# voltage_regulator.net
KiCad netlist of a schematic drawn in Altium Designer
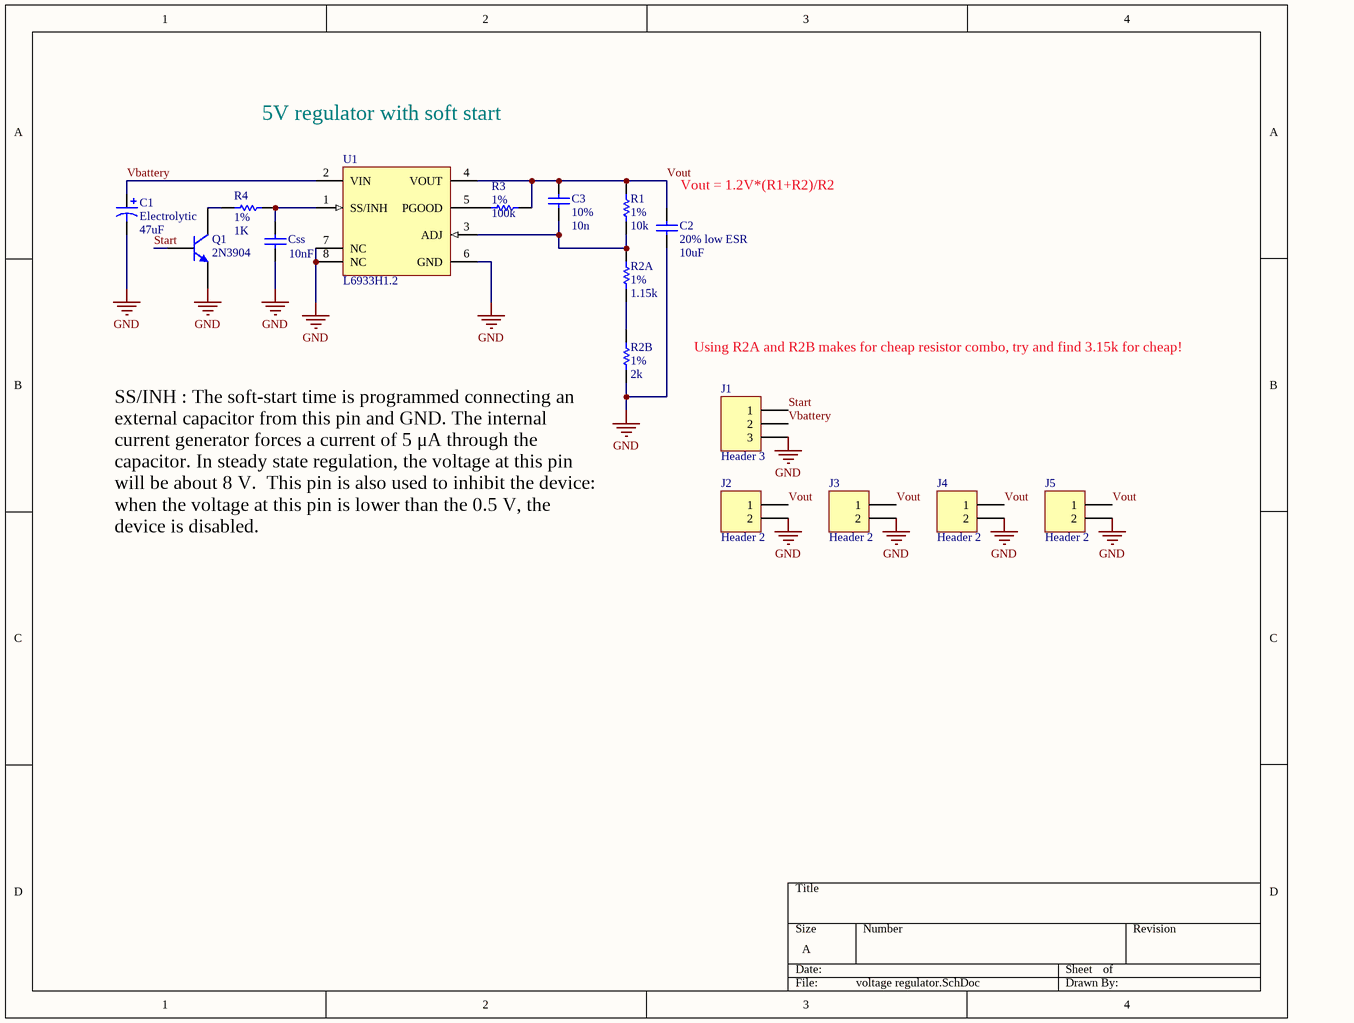
[diagram p0: voltage regulator.SchDoc]

(export (version "E")
  (design (tool "Eeschema 10.0.6"))
  (components
    (comp (ref "C1")
      (value "Electrolytic")
      (footprint "RAD-0.3")
      (description "Polarized Capacitor (Radial)")
      (fields (field (name "ALTIUM_VALUE") "47uF") (field (name "PUBLISHER") "Altium Limited"))
      (libsource (lib "Miscellaneous Devices") (part "Cap Pol1"))
    )
    (comp (ref "C2")
      (value "20% low ESR")
      (footprint "C1206")
      (description "Capacitor")
      (fields (field (name "ALTIUM_VALUE") "10uF") (field (name "PUBLISHER") "Altium Limited"))
      (libsource (lib "Miscellaneous Devices") (part "Cap"))
    )
    (comp (ref "C3")
      (value "10%")
      (footprint "6-0805_M")
      (description "Capacitor")
      (fields (field (name "ALTIUM_VALUE") "10n") (field (name "PUBLISHER") "Altium Limited"))
      (libsource (lib "Miscellaneous Devices") (part "Cap"))
    )
    (comp (ref "Css")
      (value "10nF")
      (footprint "6-0805_M")
      (description "Capacitor")
      (fields (field (name "Comment") "10%, 10 nF, 16 V (min)") (field (name "PUBLISHER") "Altium Limited"))
      (libsource (lib "Miscellaneous Devices") (part "Cap"))
    )
    (comp (ref "J1")
      (value "Header 3")
      (footprint "HDR1X3")
      (description "Header, 3-Pin")
      (fields (field (name "PUBLISHER") "Altium Limited"))
      (libsource (lib "Miscellaneous Connectors") (part "Header 3"))
    )
    (comp (ref "J2")
      (value "Header 2")
      (footprint "HDR1X2")
      (description "Header, 2-Pin")
      (fields (field (name "PUBLISHER") "Altium Limited"))
      (libsource (lib "Miscellaneous Connectors") (part "Header 2"))
    )
    (comp (ref "J3")
      (value "Header 2")
      (footprint "HDR1X2")
      (description "Header, 2-Pin")
      (fields (field (name "PUBLISHER") "Altium Limited"))
      (libsource (lib "Miscellaneous Connectors") (part "Header 2"))
    )
    (comp (ref "J4")
      (value "Header 2")
      (footprint "HDR1X2")
      (description "Header, 2-Pin")
      (fields (field (name "PUBLISHER") "Altium Limited"))
      (libsource (lib "Miscellaneous Connectors") (part "Header 2"))
    )
    (comp (ref "J5")
      (value "Header 2")
      (footprint "HDR1X2")
      (description "Header, 2-Pin")
      (fields (field (name "PUBLISHER") "Altium Limited"))
      (libsource (lib "Miscellaneous Connectors") (part "Header 2"))
    )
    (comp (ref "Q1")
      (value "2N3904")
      (footprint "TO-92A")
      (description "NPN General Purpose Amplifier")
      (fields (field (name "PUBLISHER") "Altium Limited"))
      (libsource (lib "Miscellaneous Devices") (part "2N3904"))
    )
    (comp (ref "R1")
      (value "1%")
      (footprint "6-0805_M")
      (description "Resistor")
      (fields (field (name "ALTIUM_VALUE") "10k") (field (name "PUBLISHER") "Altium Limited"))
      (libsource (lib "Miscellaneous Devices") (part "Res1"))
    )
    (comp (ref "R2A")
      (value "1%")
      (footprint "6-0805_M")
      (description "Resistor")
      (fields (field (name "ALTIUM_VALUE") "1.15k") (field (name "PUBLISHER") "Altium Limited"))
      (libsource (lib "Miscellaneous Devices") (part "Res1"))
    )
    (comp (ref "R2B")
      (value "1%")
      (footprint "6-0805_M")
      (description "Resistor")
      (fields (field (name "ALTIUM_VALUE") "2k") (field (name "PUBLISHER") "Altium Limited"))
      (libsource (lib "Miscellaneous Devices") (part "Res1"))
    )
    (comp (ref "R3")
      (value "1%")
      (footprint "6-0805_M")
      (description "Resistor")
      (fields (field (name "ALTIUM_VALUE") "100k") (field (name "PUBLISHER") "Altium Limited"))
      (libsource (lib "Miscellaneous Devices") (part "Res1"))
    )
    (comp (ref "R4")
      (value "1%")
      (footprint "6-0805_M")
      (description "Resistor")
      (fields (field (name "ALTIUM_VALUE") "1K") (field (name "PUBLISHER") "Altium Limited"))
      (libsource (lib "Miscellaneous Devices") (part "Res1"))
    )
    (comp (ref "U1")
      (value "L6933H1.2")
      (footprint "SO8_M")
      (description "High Performance 2A ULDO Linear Regulator with Soft Start, 8-Pin SO")
      (libsource (lib "Altium Content Vault") (part "CMP-0240-00057-1"))
    )
  )
  (nets
    (net (code "1") (name "/Start") (class "Default")
      (node (ref "J1") (pin "1") (pinfunction "1_1") (pintype "passive"))
      (node (ref "Q1") (pin "2") (pinfunction "B_2") (pintype "passive"))
    )
    (net (code "2") (name "/Vbattery") (class "Default")
      (node (ref "C1") (pin "1") (pinfunction "1_1") (pintype "passive"))
      (node (ref "J1") (pin "2") (pinfunction "2_2") (pintype "passive"))
      (node (ref "U1") (pin "2") (pinfunction "VIN_2") (pintype "power_in"))
    )
    (net (code "3") (name "/Vout") (class "Default")
      (node (ref "C2") (pin "2") (pinfunction "2_2") (pintype "passive"))
      (node (ref "C3") (pin "2") (pinfunction "2_2") (pintype "passive"))
      (node (ref "J2") (pin "1") (pinfunction "1_1") (pintype "passive"))
      (node (ref "J3") (pin "1") (pinfunction "1_1") (pintype "passive"))
      (node (ref "J4") (pin "1") (pinfunction "1_1") (pintype "passive"))
      (node (ref "J5") (pin "1") (pinfunction "1_1") (pintype "passive"))
      (node (ref "R1") (pin "2") (pinfunction "2_2") (pintype "passive"))
      (node (ref "R3") (pin "2") (pinfunction "2_2") (pintype "passive"))
      (node (ref "U1") (pin "4") (pinfunction "VOUT_4") (pintype "power_in"))
    )
    (net (code "4") (name "GND") (class "Default")
      (node (ref "C1") (pin "2") (pinfunction "2_2") (pintype "passive"))
      (node (ref "C2") (pin "1") (pinfunction "1_1") (pintype "passive"))
      (node (ref "Css") (pin "1") (pinfunction "1_1") (pintype "passive"))
      (node (ref "J1") (pin "3") (pinfunction "3_3") (pintype "passive"))
      (node (ref "J2") (pin "2") (pinfunction "2_2") (pintype "passive"))
      (node (ref "J3") (pin "2") (pinfunction "2_2") (pintype "passive"))
      (node (ref "J4") (pin "2") (pinfunction "2_2") (pintype "passive"))
      (node (ref "J5") (pin "2") (pinfunction "2_2") (pintype "passive"))
      (node (ref "Q1") (pin "1") (pinfunction "E_1") (pintype "passive"))
      (node (ref "R2B") (pin "1") (pinfunction "1_1") (pintype "passive"))
      (node (ref "U1") (pin "6") (pinfunction "GND_6") (pintype "power_in"))
      (node (ref "U1") (pin "7") (pinfunction "NC_7") (pintype "passive"))
      (node (ref "U1") (pin "8") (pinfunction "NC_8") (pintype "passive"))
    )
    (net (code "5") (name "Net-(Q1-C)") (class "Default")
      (node (ref "Q1") (pin "3") (pinfunction "C_3") (pintype "passive"))
      (node (ref "R4") (pin "1") (pinfunction "1_1") (pintype "passive"))
    )
    (net (code "6") (name "Net-(R2A-Pad1)") (class "Default")
      (node (ref "R2A") (pin "1") (pinfunction "1_1") (pintype "passive"))
      (node (ref "R2B") (pin "2") (pinfunction "2_2") (pintype "passive"))
    )
    (net (code "7") (name "Net-(U1-ADJ)") (class "Default")
      (node (ref "C3") (pin "1") (pinfunction "1_1") (pintype "passive"))
      (node (ref "R1") (pin "1") (pinfunction "1_1") (pintype "passive"))
      (node (ref "R2A") (pin "2") (pinfunction "2_2") (pintype "passive"))
      (node (ref "U1") (pin "3") (pinfunction "ADJ_3") (pintype "input"))
    )
    (net (code "8") (name "Net-(U1-PGOOD)") (class "Default")
      (node (ref "R3") (pin "1") (pinfunction "1_1") (pintype "passive"))
      (node (ref "U1") (pin "5") (pinfunction "PGOOD_5") (pintype "open_collector"))
    )
    (net (code "9") (name "Net-(U1-SS{slash}INH)") (class "Default")
      (node (ref "Css") (pin "2") (pinfunction "2_2") (pintype "passive"))
      (node (ref "R4") (pin "2") (pinfunction "2_2") (pintype "passive"))
      (node (ref "U1") (pin "1") (pinfunction "SS/INH_1") (pintype "input"))
    )
  )
)
